# schematic.net
KiCad netlist of a schematic drawn in EAGLE
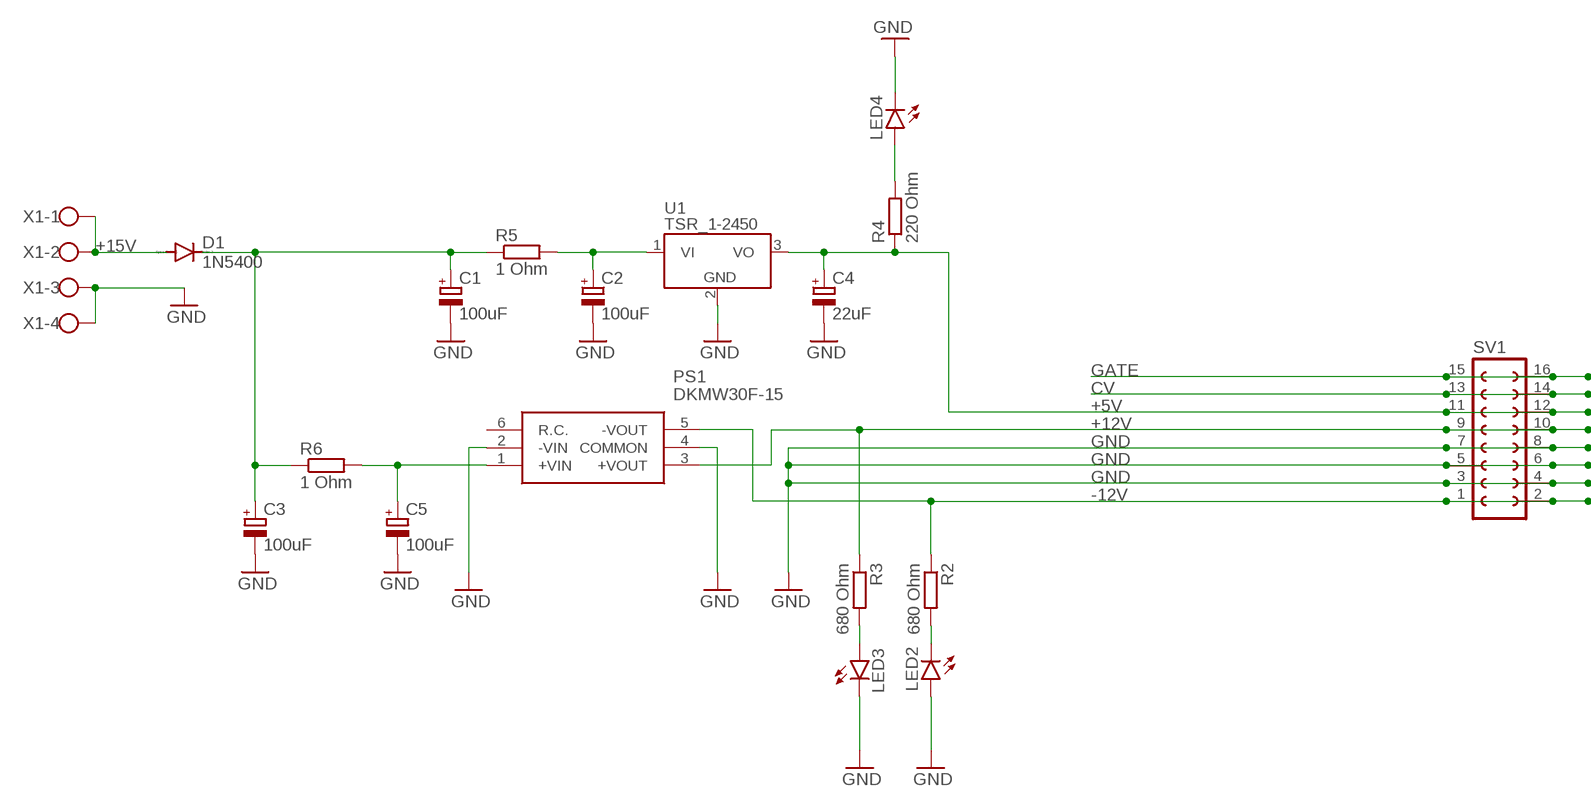
[diagram p0: schematic, sheet 1, part 1 of 2]
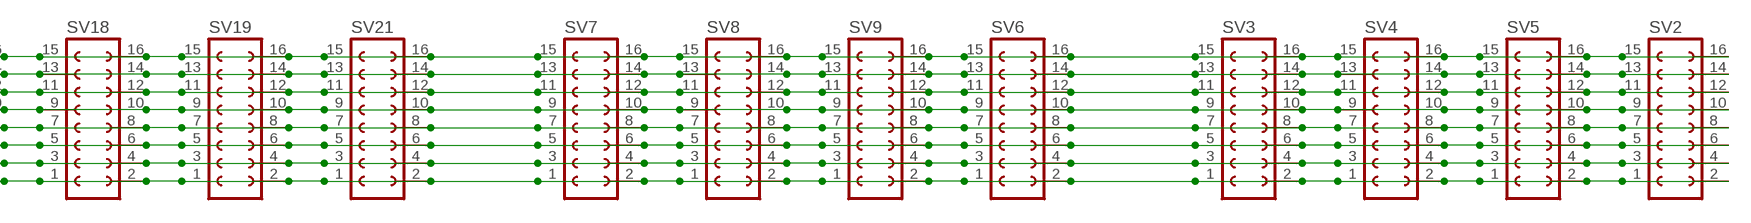
[diagram p1: schematic, sheet 1, part 2 of 2]

(export (version "E")
  (design (tool "Eeschema 10.0.6"))
  (components
    (comp (ref "C1")
      (value "100uF")
      (footprint "eagle-import:E3,5-8")
      (libsource (lib "eagle-import") (part "CPOL-EUE3.5-8"))
    )
    (comp (ref "C2")
      (value "100uF")
      (footprint "eagle-import:E3,5-8")
      (libsource (lib "eagle-import") (part "CPOL-EUE3.5-8"))
    )
    (comp (ref "C3")
      (value "100uF")
      (footprint "eagle-import:E3,5-8")
      (libsource (lib "eagle-import") (part "CPOL-EUE3.5-8"))
    )
    (comp (ref "C4")
      (value "22uF")
      (footprint "eagle-import:E2,5-5")
      (libsource (lib "eagle-import") (part "CPOL-EUE2.5-5"))
    )
    (comp (ref "C5")
      (value "100uF")
      (footprint "eagle-import:E3,5-8")
      (libsource (lib "eagle-import") (part "CPOL-EUE3.5-8"))
    )
    (comp (ref "D1")
      (value "1N5400")
      (footprint "eagle-import:DO201-15")
      (libsource (lib "eagle-import") (part "1N5400"))
    )
    (comp (ref "LED2")
      (value "LED3MM")
      (footprint "eagle-import:LED3MM")
      (libsource (lib "eagle-import") (part "LED3MM"))
    )
    (comp (ref "LED3")
      (value "LED3MM")
      (footprint "eagle-import:LED3MM")
      (libsource (lib "eagle-import") (part "LED3MM"))
    )
    (comp (ref "LED4")
      (value "LED3MM")
      (footprint "eagle-import:LED3MM")
      (libsource (lib "eagle-import") (part "LED3MM"))
    )
    (comp (ref "PS1")
      (value "DKMW30F-15")
      (footprint "eagle-import:DKMW30F15")
      (fields (field (name "MOUSER_PART_NUMBER") "709-DKMW30F-15"))
      (libsource (lib "eagle-import") (part "DKMW30F-15"))
    )
    (comp (ref "R2")
      (value "680 Ohm")
      (footprint "eagle-import:0207_10")
      (libsource (lib "eagle-import") (part "R-EU_0207/10"))
    )
    (comp (ref "R3")
      (value "680 Ohm")
      (footprint "eagle-import:0207_10")
      (libsource (lib "eagle-import") (part "R-EU_0207/10"))
    )
    (comp (ref "R4")
      (value "220 Ohm")
      (footprint "eagle-import:0207_10")
      (libsource (lib "eagle-import") (part "R-EU_0207/10"))
    )
    (comp (ref "R5")
      (value "1 Ohm")
      (footprint "eagle-import:0207_10")
      (libsource (lib "eagle-import") (part "R-EU_0207/10"))
    )
    (comp (ref "R6")
      (value "1 Ohm")
      (footprint "eagle-import:0207_10")
      (libsource (lib "eagle-import") (part "R-EU_0207/10"))
    )
    (comp (ref "SV1")
      (value "FE08-2")
      (footprint "eagle-import:FE08-2")
      (libsource (lib "eagle-import") (part "FE08-2"))
    )
    (comp (ref "SV2")
      (value "FE08-2")
      (footprint "eagle-import:FE08-2")
      (libsource (lib "eagle-import") (part "FE08-2"))
    )
    (comp (ref "SV3")
      (value "FE08-2")
      (footprint "eagle-import:FE08-2")
      (libsource (lib "eagle-import") (part "FE08-2"))
    )
    (comp (ref "SV4")
      (value "FE08-2")
      (footprint "eagle-import:FE08-2")
      (libsource (lib "eagle-import") (part "FE08-2"))
    )
    (comp (ref "SV5")
      (value "FE08-2")
      (footprint "eagle-import:FE08-2")
      (libsource (lib "eagle-import") (part "FE08-2"))
    )
    (comp (ref "SV6")
      (value "FE08-2")
      (footprint "eagle-import:FE08-2")
      (libsource (lib "eagle-import") (part "FE08-2"))
    )
    (comp (ref "SV7")
      (value "FE08-2")
      (footprint "eagle-import:FE08-2")
      (libsource (lib "eagle-import") (part "FE08-2"))
    )
    (comp (ref "SV8")
      (value "FE08-2")
      (footprint "eagle-import:FE08-2")
      (libsource (lib "eagle-import") (part "FE08-2"))
    )
    (comp (ref "SV9")
      (value "FE08-2")
      (footprint "eagle-import:FE08-2")
      (libsource (lib "eagle-import") (part "FE08-2"))
    )
    (comp (ref "SV18")
      (value "FE08-2")
      (footprint "eagle-import:FE08-2")
      (libsource (lib "eagle-import") (part "FE08-2"))
    )
    (comp (ref "SV19")
      (value "FE08-2")
      (footprint "eagle-import:FE08-2")
      (libsource (lib "eagle-import") (part "FE08-2"))
    )
    (comp (ref "SV21")
      (value "FE08-2")
      (footprint "eagle-import:FE08-2")
      (libsource (lib "eagle-import") (part "FE08-2"))
    )
    (comp (ref "U1")
      (value "TSR_1-2450")
      (footprint "eagle-import:TSR-1")
      (libsource (lib "eagle-import") (part "TSR_1-2450"))
    )
    (comp (ref "X1")
      (value "W237-4")
      (footprint "eagle-import:W237-4")
      (libsource (lib "eagle-import") (part "W237-4"))
    )
  )
  (nets
    (net (code "1") (name "/+5V") (class "Default")
      (node (ref "C4") (pin "+") (pinfunction "+_+") (pintype "passive"))
      (node (ref "R4") (pin "1") (pinfunction "1_1") (pintype "passive"))
      (node (ref "SV1") (pin "11") (pinfunction "11_11") (pintype "passive"))
      (node (ref "SV1") (pin "12") (pinfunction "12_12") (pintype "passive"))
      (node (ref "SV18") (pin "11") (pinfunction "11_11") (pintype "passive"))
      (node (ref "SV18") (pin "12") (pinfunction "12_12") (pintype "passive"))
      (node (ref "SV19") (pin "11") (pinfunction "11_11") (pintype "passive"))
      (node (ref "SV19") (pin "12") (pinfunction "12_12") (pintype "passive"))
      (node (ref "SV2") (pin "11") (pinfunction "11_11") (pintype "passive"))
      (node (ref "SV2") (pin "12") (pinfunction "12_12") (pintype "passive"))
      (node (ref "SV21") (pin "11") (pinfunction "11_11") (pintype "passive"))
      (node (ref "SV21") (pin "12") (pinfunction "12_12") (pintype "passive"))
      (node (ref "SV3") (pin "11") (pinfunction "11_11") (pintype "passive"))
      (node (ref "SV3") (pin "12") (pinfunction "12_12") (pintype "passive"))
      (node (ref "SV4") (pin "11") (pinfunction "11_11") (pintype "passive"))
      (node (ref "SV4") (pin "12") (pinfunction "12_12") (pintype "passive"))
      (node (ref "SV5") (pin "11") (pinfunction "11_11") (pintype "passive"))
      (node (ref "SV5") (pin "12") (pinfunction "12_12") (pintype "passive"))
      (node (ref "SV6") (pin "11") (pinfunction "11_11") (pintype "passive"))
      (node (ref "SV6") (pin "12") (pinfunction "12_12") (pintype "passive"))
      (node (ref "SV7") (pin "11") (pinfunction "11_11") (pintype "passive"))
      (node (ref "SV7") (pin "12") (pinfunction "12_12") (pintype "passive"))
      (node (ref "SV8") (pin "11") (pinfunction "11_11") (pintype "passive"))
      (node (ref "SV8") (pin "12") (pinfunction "12_12") (pintype "passive"))
      (node (ref "SV9") (pin "11") (pinfunction "11_11") (pintype "passive"))
      (node (ref "SV9") (pin "12") (pinfunction "12_12") (pintype "passive"))
      (node (ref "U1") (pin "3") (pinfunction "VO_3") (pintype "power_in"))
    )
    (net (code "2") (name "/+12V") (class "Default")
      (node (ref "PS1") (pin "3") (pinfunction "+VOUT_3") (pintype "bidirectional"))
      (node (ref "R3") (pin "1") (pinfunction "1_1") (pintype "passive"))
      (node (ref "SV1") (pin "10") (pinfunction "10_10") (pintype "passive"))
      (node (ref "SV1") (pin "9") (pinfunction "9_9") (pintype "passive"))
      (node (ref "SV18") (pin "10") (pinfunction "10_10") (pintype "passive"))
      (node (ref "SV18") (pin "9") (pinfunction "9_9") (pintype "passive"))
      (node (ref "SV19") (pin "10") (pinfunction "10_10") (pintype "passive"))
      (node (ref "SV19") (pin "9") (pinfunction "9_9") (pintype "passive"))
      (node (ref "SV2") (pin "10") (pinfunction "10_10") (pintype "passive"))
      (node (ref "SV2") (pin "9") (pinfunction "9_9") (pintype "passive"))
      (node (ref "SV21") (pin "10") (pinfunction "10_10") (pintype "passive"))
      (node (ref "SV21") (pin "9") (pinfunction "9_9") (pintype "passive"))
      (node (ref "SV3") (pin "10") (pinfunction "10_10") (pintype "passive"))
      (node (ref "SV3") (pin "9") (pinfunction "9_9") (pintype "passive"))
      (node (ref "SV4") (pin "10") (pinfunction "10_10") (pintype "passive"))
      (node (ref "SV4") (pin "9") (pinfunction "9_9") (pintype "passive"))
      (node (ref "SV5") (pin "10") (pinfunction "10_10") (pintype "passive"))
      (node (ref "SV5") (pin "9") (pinfunction "9_9") (pintype "passive"))
      (node (ref "SV6") (pin "10") (pinfunction "10_10") (pintype "passive"))
      (node (ref "SV6") (pin "9") (pinfunction "9_9") (pintype "passive"))
      (node (ref "SV7") (pin "10") (pinfunction "10_10") (pintype "passive"))
      (node (ref "SV7") (pin "9") (pinfunction "9_9") (pintype "passive"))
      (node (ref "SV8") (pin "10") (pinfunction "10_10") (pintype "passive"))
      (node (ref "SV8") (pin "9") (pinfunction "9_9") (pintype "passive"))
      (node (ref "SV9") (pin "10") (pinfunction "10_10") (pintype "passive"))
      (node (ref "SV9") (pin "9") (pinfunction "9_9") (pintype "passive"))
    )
    (net (code "3") (name "/+15V") (class "Default")
      (node (ref "D1") (pin "A") (pinfunction "A_A") (pintype "passive"))
      (node (ref "X1") (pin "1") (pinfunction "KL_1") (pintype "passive"))
      (node (ref "X1") (pin "2") (pinfunction "KL_2") (pintype "passive"))
    )
    (net (code "4") (name "/-12V") (class "Default")
      (node (ref "PS1") (pin "5") (pinfunction "-VOUT_5") (pintype "bidirectional"))
      (node (ref "R2") (pin "1") (pinfunction "1_1") (pintype "passive"))
      (node (ref "SV1") (pin "1") (pinfunction "1_1") (pintype "passive"))
      (node (ref "SV1") (pin "2") (pinfunction "2_2") (pintype "passive"))
      (node (ref "SV18") (pin "1") (pinfunction "1_1") (pintype "passive"))
      (node (ref "SV18") (pin "2") (pinfunction "2_2") (pintype "passive"))
      (node (ref "SV19") (pin "1") (pinfunction "1_1") (pintype "passive"))
      (node (ref "SV19") (pin "2") (pinfunction "2_2") (pintype "passive"))
      (node (ref "SV2") (pin "1") (pinfunction "1_1") (pintype "passive"))
      (node (ref "SV2") (pin "2") (pinfunction "2_2") (pintype "passive"))
      (node (ref "SV21") (pin "1") (pinfunction "1_1") (pintype "passive"))
      (node (ref "SV21") (pin "2") (pinfunction "2_2") (pintype "passive"))
      (node (ref "SV3") (pin "1") (pinfunction "1_1") (pintype "passive"))
      (node (ref "SV3") (pin "2") (pinfunction "2_2") (pintype "passive"))
      (node (ref "SV4") (pin "1") (pinfunction "1_1") (pintype "passive"))
      (node (ref "SV4") (pin "2") (pinfunction "2_2") (pintype "passive"))
      (node (ref "SV5") (pin "1") (pinfunction "1_1") (pintype "passive"))
      (node (ref "SV5") (pin "2") (pinfunction "2_2") (pintype "passive"))
      (node (ref "SV6") (pin "1") (pinfunction "1_1") (pintype "passive"))
      (node (ref "SV6") (pin "2") (pinfunction "2_2") (pintype "passive"))
      (node (ref "SV7") (pin "1") (pinfunction "1_1") (pintype "passive"))
      (node (ref "SV7") (pin "2") (pinfunction "2_2") (pintype "passive"))
      (node (ref "SV8") (pin "1") (pinfunction "1_1") (pintype "passive"))
      (node (ref "SV8") (pin "2") (pinfunction "2_2") (pintype "passive"))
      (node (ref "SV9") (pin "1") (pinfunction "1_1") (pintype "passive"))
      (node (ref "SV9") (pin "2") (pinfunction "2_2") (pintype "passive"))
    )
    (net (code "5") (name "/CV") (class "Default")
      (node (ref "SV1") (pin "13") (pinfunction "13_13") (pintype "passive"))
      (node (ref "SV1") (pin "14") (pinfunction "14_14") (pintype "passive"))
      (node (ref "SV18") (pin "13") (pinfunction "13_13") (pintype "passive"))
      (node (ref "SV18") (pin "14") (pinfunction "14_14") (pintype "passive"))
      (node (ref "SV19") (pin "13") (pinfunction "13_13") (pintype "passive"))
      (node (ref "SV19") (pin "14") (pinfunction "14_14") (pintype "passive"))
      (node (ref "SV2") (pin "13") (pinfunction "13_13") (pintype "passive"))
      (node (ref "SV2") (pin "14") (pinfunction "14_14") (pintype "passive"))
      (node (ref "SV21") (pin "13") (pinfunction "13_13") (pintype "passive"))
      (node (ref "SV21") (pin "14") (pinfunction "14_14") (pintype "passive"))
      (node (ref "SV3") (pin "13") (pinfunction "13_13") (pintype "passive"))
      (node (ref "SV3") (pin "14") (pinfunction "14_14") (pintype "passive"))
      (node (ref "SV4") (pin "13") (pinfunction "13_13") (pintype "passive"))
      (node (ref "SV4") (pin "14") (pinfunction "14_14") (pintype "passive"))
      (node (ref "SV5") (pin "13") (pinfunction "13_13") (pintype "passive"))
      (node (ref "SV5") (pin "14") (pinfunction "14_14") (pintype "passive"))
      (node (ref "SV6") (pin "13") (pinfunction "13_13") (pintype "passive"))
      (node (ref "SV6") (pin "14") (pinfunction "14_14") (pintype "passive"))
      (node (ref "SV7") (pin "13") (pinfunction "13_13") (pintype "passive"))
      (node (ref "SV7") (pin "14") (pinfunction "14_14") (pintype "passive"))
      (node (ref "SV8") (pin "13") (pinfunction "13_13") (pintype "passive"))
      (node (ref "SV8") (pin "14") (pinfunction "14_14") (pintype "passive"))
      (node (ref "SV9") (pin "13") (pinfunction "13_13") (pintype "passive"))
      (node (ref "SV9") (pin "14") (pinfunction "14_14") (pintype "passive"))
    )
    (net (code "6") (name "/GATE") (class "Default")
      (node (ref "SV1") (pin "15") (pinfunction "15_15") (pintype "passive"))
      (node (ref "SV1") (pin "16") (pinfunction "16_16") (pintype "passive"))
      (node (ref "SV18") (pin "15") (pinfunction "15_15") (pintype "passive"))
      (node (ref "SV18") (pin "16") (pinfunction "16_16") (pintype "passive"))
      (node (ref "SV19") (pin "15") (pinfunction "15_15") (pintype "passive"))
      (node (ref "SV19") (pin "16") (pinfunction "16_16") (pintype "passive"))
      (node (ref "SV2") (pin "15") (pinfunction "15_15") (pintype "passive"))
      (node (ref "SV2") (pin "16") (pinfunction "16_16") (pintype "passive"))
      (node (ref "SV21") (pin "15") (pinfunction "15_15") (pintype "passive"))
      (node (ref "SV21") (pin "16") (pinfunction "16_16") (pintype "passive"))
      (node (ref "SV3") (pin "15") (pinfunction "15_15") (pintype "passive"))
      (node (ref "SV3") (pin "16") (pinfunction "16_16") (pintype "passive"))
      (node (ref "SV4") (pin "15") (pinfunction "15_15") (pintype "passive"))
      (node (ref "SV4") (pin "16") (pinfunction "16_16") (pintype "passive"))
      (node (ref "SV5") (pin "15") (pinfunction "15_15") (pintype "passive"))
      (node (ref "SV5") (pin "16") (pinfunction "16_16") (pintype "passive"))
      (node (ref "SV6") (pin "15") (pinfunction "15_15") (pintype "passive"))
      (node (ref "SV6") (pin "16") (pinfunction "16_16") (pintype "passive"))
      (node (ref "SV7") (pin "15") (pinfunction "15_15") (pintype "passive"))
      (node (ref "SV7") (pin "16") (pinfunction "16_16") (pintype "passive"))
      (node (ref "SV8") (pin "15") (pinfunction "15_15") (pintype "passive"))
      (node (ref "SV8") (pin "16") (pinfunction "16_16") (pintype "passive"))
      (node (ref "SV9") (pin "15") (pinfunction "15_15") (pintype "passive"))
      (node (ref "SV9") (pin "16") (pinfunction "16_16") (pintype "passive"))
    )
    (net (code "7") (name "GND") (class "Default")
      (node (ref "C1") (pin "-") (pinfunction "-_-") (pintype "passive"))
      (node (ref "C2") (pin "-") (pinfunction "-_-") (pintype "passive"))
      (node (ref "C3") (pin "-") (pinfunction "-_-") (pintype "passive"))
      (node (ref "C4") (pin "-") (pinfunction "-_-") (pintype "passive"))
      (node (ref "C5") (pin "-") (pinfunction "-_-") (pintype "passive"))
      (node (ref "LED2") (pin "A") (pinfunction "A_A") (pintype "passive"))
      (node (ref "LED3") (pin "K") (pinfunction "C_K") (pintype "passive"))
      (node (ref "LED4") (pin "K") (pinfunction "C_K") (pintype "passive"))
      (node (ref "PS1") (pin "2") (pinfunction "-VIN_2") (pintype "bidirectional"))
      (node (ref "PS1") (pin "4") (pinfunction "COMMON_4") (pintype "bidirectional"))
      (node (ref "SV1") (pin "3") (pinfunction "3_3") (pintype "passive"))
      (node (ref "SV1") (pin "4") (pinfunction "4_4") (pintype "passive"))
      (node (ref "SV1") (pin "5") (pinfunction "5_5") (pintype "passive"))
      (node (ref "SV1") (pin "6") (pinfunction "6_6") (pintype "passive"))
      (node (ref "SV1") (pin "7") (pinfunction "7_7") (pintype "passive"))
      (node (ref "SV1") (pin "8") (pinfunction "8_8") (pintype "passive"))
      (node (ref "SV18") (pin "3") (pinfunction "3_3") (pintype "passive"))
      (node (ref "SV18") (pin "4") (pinfunction "4_4") (pintype "passive"))
      (node (ref "SV18") (pin "5") (pinfunction "5_5") (pintype "passive"))
      (node (ref "SV18") (pin "6") (pinfunction "6_6") (pintype "passive"))
      (node (ref "SV18") (pin "7") (pinfunction "7_7") (pintype "passive"))
      (node (ref "SV18") (pin "8") (pinfunction "8_8") (pintype "passive"))
      (node (ref "SV19") (pin "3") (pinfunction "3_3") (pintype "passive"))
      (node (ref "SV19") (pin "4") (pinfunction "4_4") (pintype "passive"))
      (node (ref "SV19") (pin "5") (pinfunction "5_5") (pintype "passive"))
      (node (ref "SV19") (pin "6") (pinfunction "6_6") (pintype "passive"))
      (node (ref "SV19") (pin "7") (pinfunction "7_7") (pintype "passive"))
      (node (ref "SV19") (pin "8") (pinfunction "8_8") (pintype "passive"))
      (node (ref "SV2") (pin "3") (pinfunction "3_3") (pintype "passive"))
      (node (ref "SV2") (pin "4") (pinfunction "4_4") (pintype "passive"))
      (node (ref "SV2") (pin "5") (pinfunction "5_5") (pintype "passive"))
      (node (ref "SV2") (pin "6") (pinfunction "6_6") (pintype "passive"))
      (node (ref "SV2") (pin "7") (pinfunction "7_7") (pintype "passive"))
      (node (ref "SV2") (pin "8") (pinfunction "8_8") (pintype "passive"))
      (node (ref "SV21") (pin "3") (pinfunction "3_3") (pintype "passive"))
      (node (ref "SV21") (pin "4") (pinfunction "4_4") (pintype "passive"))
      (node (ref "SV21") (pin "5") (pinfunction "5_5") (pintype "passive"))
      (node (ref "SV21") (pin "6") (pinfunction "6_6") (pintype "passive"))
      (node (ref "SV21") (pin "7") (pinfunction "7_7") (pintype "passive"))
      (node (ref "SV21") (pin "8") (pinfunction "8_8") (pintype "passive"))
      (node (ref "SV3") (pin "3") (pinfunction "3_3") (pintype "passive"))
      (node (ref "SV3") (pin "4") (pinfunction "4_4") (pintype "passive"))
      (node (ref "SV3") (pin "5") (pinfunction "5_5") (pintype "passive"))
      (node (ref "SV3") (pin "6") (pinfunction "6_6") (pintype "passive"))
      (node (ref "SV3") (pin "7") (pinfunction "7_7") (pintype "passive"))
      (node (ref "SV3") (pin "8") (pinfunction "8_8") (pintype "passive"))
      (node (ref "SV4") (pin "3") (pinfunction "3_3") (pintype "passive"))
      (node (ref "SV4") (pin "4") (pinfunction "4_4") (pintype "passive"))
      (node (ref "SV4") (pin "5") (pinfunction "5_5") (pintype "passive"))
      (node (ref "SV4") (pin "6") (pinfunction "6_6") (pintype "passive"))
      (node (ref "SV4") (pin "7") (pinfunction "7_7") (pintype "passive"))
      (node (ref "SV4") (pin "8") (pinfunction "8_8") (pintype "passive"))
      (node (ref "SV5") (pin "3") (pinfunction "3_3") (pintype "passive"))
      (node (ref "SV5") (pin "4") (pinfunction "4_4") (pintype "passive"))
      (node (ref "SV5") (pin "5") (pinfunction "5_5") (pintype "passive"))
      (node (ref "SV5") (pin "6") (pinfunction "6_6") (pintype "passive"))
      (node (ref "SV5") (pin "7") (pinfunction "7_7") (pintype "passive"))
      (node (ref "SV5") (pin "8") (pinfunction "8_8") (pintype "passive"))
      (node (ref "SV6") (pin "3") (pinfunction "3_3") (pintype "passive"))
      (node (ref "SV6") (pin "4") (pinfunction "4_4") (pintype "passive"))
      (node (ref "SV6") (pin "5") (pinfunction "5_5") (pintype "passive"))
      (node (ref "SV6") (pin "6") (pinfunction "6_6") (pintype "passive"))
      (node (ref "SV6") (pin "7") (pinfunction "7_7") (pintype "passive"))
      (node (ref "SV6") (pin "8") (pinfunction "8_8") (pintype "passive"))
      (node (ref "SV7") (pin "3") (pinfunction "3_3") (pintype "passive"))
      (node (ref "SV7") (pin "4") (pinfunction "4_4") (pintype "passive"))
      (node (ref "SV7") (pin "5") (pinfunction "5_5") (pintype "passive"))
      (node (ref "SV7") (pin "6") (pinfunction "6_6") (pintype "passive"))
      (node (ref "SV7") (pin "7") (pinfunction "7_7") (pintype "passive"))
      (node (ref "SV7") (pin "8") (pinfunction "8_8") (pintype "passive"))
      (node (ref "SV8") (pin "3") (pinfunction "3_3") (pintype "passive"))
      (node (ref "SV8") (pin "4") (pinfunction "4_4") (pintype "passive"))
      (node (ref "SV8") (pin "5") (pinfunction "5_5") (pintype "passive"))
      (node (ref "SV8") (pin "6") (pinfunction "6_6") (pintype "passive"))
      (node (ref "SV8") (pin "7") (pinfunction "7_7") (pintype "passive"))
      (node (ref "SV8") (pin "8") (pinfunction "8_8") (pintype "passive"))
      (node (ref "SV9") (pin "3") (pinfunction "3_3") (pintype "passive"))
      (node (ref "SV9") (pin "4") (pinfunction "4_4") (pintype "passive"))
      (node (ref "SV9") (pin "5") (pinfunction "5_5") (pintype "passive"))
      (node (ref "SV9") (pin "6") (pinfunction "6_6") (pintype "passive"))
      (node (ref "SV9") (pin "7") (pinfunction "7_7") (pintype "passive"))
      (node (ref "SV9") (pin "8") (pinfunction "8_8") (pintype "passive"))
      (node (ref "U1") (pin "2") (pinfunction "GND_2") (pintype "power_in"))
      (node (ref "X1") (pin "3") (pinfunction "KL_3") (pintype "passive"))
      (node (ref "X1") (pin "4") (pinfunction "KL_4") (pintype "passive"))
    )
    (net (code "8") (name "Net-(C1-Pad+)") (class "Default")
      (node (ref "C1") (pin "+") (pinfunction "+_+") (pintype "passive"))
      (node (ref "C3") (pin "+") (pinfunction "+_+") (pintype "passive"))
      (node (ref "D1") (pin "C") (pinfunction "C_C") (pintype "passive"))
      (node (ref "R5") (pin "1") (pinfunction "1_1") (pintype "passive"))
      (node (ref "R6") (pin "1") (pinfunction "1_1") (pintype "passive"))
    )
    (net (code "9") (name "Net-(LED2-C)") (class "Default")
      (node (ref "LED2") (pin "K") (pinfunction "C_K") (pintype "passive"))
      (node (ref "R2") (pin "2") (pinfunction "2_2") (pintype "passive"))
    )
    (net (code "10") (name "Net-(LED3-PadA)") (class "Default")
      (node (ref "LED3") (pin "A") (pinfunction "A_A") (pintype "passive"))
      (node (ref "R3") (pin "2") (pinfunction "2_2") (pintype "passive"))
    )
    (net (code "11") (name "Net-(LED4-PadA)") (class "Default")
      (node (ref "LED4") (pin "A") (pinfunction "A_A") (pintype "passive"))
      (node (ref "R4") (pin "2") (pinfunction "2_2") (pintype "passive"))
    )
    (net (code "12") (name "Net-(PS1-+VIN)") (class "Default")
      (node (ref "C5") (pin "+") (pinfunction "+_+") (pintype "passive"))
      (node (ref "PS1") (pin "1") (pinfunction "+VIN_1") (pintype "bidirectional"))
      (node (ref "R6") (pin "2") (pinfunction "2_2") (pintype "passive"))
    )
    (net (code "13") (name "Net-(U1-VI)") (class "Default")
      (node (ref "C2") (pin "+") (pinfunction "+_+") (pintype "passive"))
      (node (ref "R5") (pin "2") (pinfunction "2_2") (pintype "passive"))
      (node (ref "U1") (pin "1") (pinfunction "VI_1") (pintype "power_in"))
    )
    (net (code "14") (name "unconnected-(PS1-R.C.-Pad6)") (class "Default")
      (node (ref "PS1") (pin "6") (pinfunction "R.C._6") (pintype "bidirectional"))
    )
  )
)
